# fDrive_RP2040.net
KiCad netlist of a schematic drawn in EAGLE
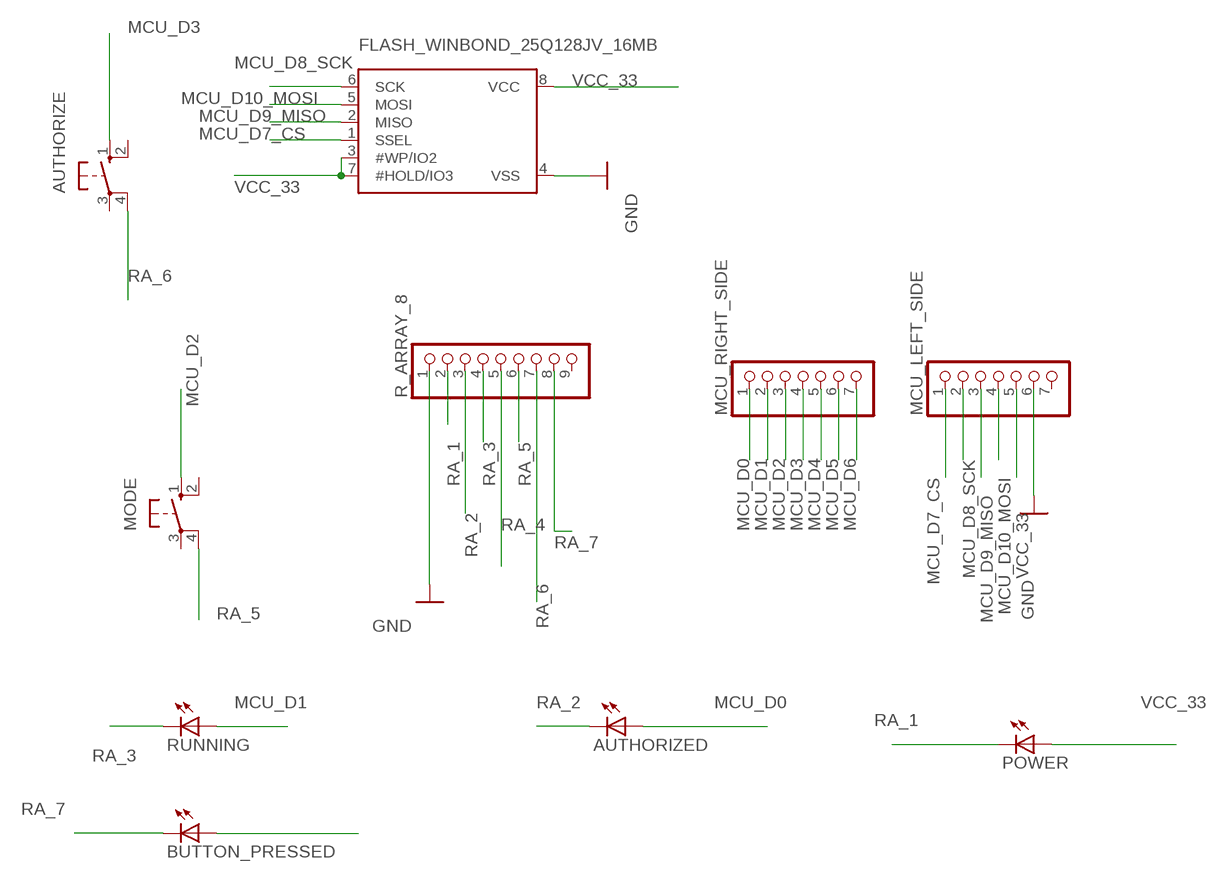
[diagram p0: schematic, sheet 1]

(export (version "E")
  (design (tool "Eeschema 10.0.6"))
  (components
    (comp (ref "AUTHORIZE")
      (value "10-XX")
      (footprint "eagle-import:B3F-10XX")
      (fields (field (name "MPN") "B3F-1000"))
      (libsource (lib "eagle-import") (part "10-XX"))
    )
    (comp (ref "AUTHORIZED")
      (value "LEDSMT1206")
      (footprint "eagle-import:1206")
      (libsource (lib "eagle-import") (part "LEDSMT1206"))
    )
    (comp (ref "BUTTON_PRESSED")
      (value "LEDSMT1206")
      (footprint "eagle-import:1206")
      (libsource (lib "eagle-import") (part "LEDSMT1206"))
    )
    (comp (ref "FLASH_WINBOND_25Q128JV_16MB")
      (value "SPIFLASH_SOIC8208MIL")
      (footprint "eagle-import:SOIC8_208MIL")
      (libsource (lib "eagle-import") (part "SPIFLASH_SOIC8208MIL"))
    )
    (comp (ref "MCU_LEFT_SIDE")
      (value "PINHD-1X7")
      (footprint "eagle-import:1X07")
      (libsource (lib "eagle-import") (part "PINHD-1X7"))
    )
    (comp (ref "MCU_RIGHT_SIDE")
      (value "PINHD-1X7")
      (footprint "eagle-import:1X07")
      (libsource (lib "eagle-import") (part "PINHD-1X7"))
    )
    (comp (ref "MODE")
      (value "10-XX")
      (footprint "eagle-import:B3F-10XX")
      (fields (field (name "MPN") "B3F-1000"))
      (libsource (lib "eagle-import") (part "10-XX"))
    )
    (comp (ref "POWER")
      (value "LEDSMT1206")
      (footprint "eagle-import:1206")
      (libsource (lib "eagle-import") (part "LEDSMT1206"))
    )
    (comp (ref "RUNNING")
      (value "LEDSMT1206")
      (footprint "eagle-import:1206")
      (libsource (lib "eagle-import") (part "LEDSMT1206"))
    )
    (comp (ref "R_ARRAY_8")
      (value "PINHD-1X9")
      (footprint "eagle-import:1X09-BIG")
      (libsource (lib "eagle-import") (part "PINHD-1X9"))
    )
  )
  (nets
    (net (code "1") (name "/MCU_D0") (class "Default")
      (node (ref "AUTHORIZED") (pin "A") (pinfunction "A_A") (pintype "passive"))
      (node (ref "MCU_RIGHT_SIDE") (pin "1") (pinfunction "1_1") (pintype "passive"))
    )
    (net (code "2") (name "/MCU_D1") (class "Default")
      (node (ref "MCU_RIGHT_SIDE") (pin "2") (pinfunction "2_2") (pintype "passive"))
      (node (ref "RUNNING") (pin "A") (pinfunction "A_A") (pintype "passive"))
    )
    (net (code "3") (name "/MCU_D2") (class "Default")
      (node (ref "MCU_RIGHT_SIDE") (pin "3") (pinfunction "3_3") (pintype "passive"))
      (node (ref "MODE") (pin "1") (pinfunction "S_1") (pintype "passive"))
    )
    (net (code "4") (name "/MCU_D3") (class "Default")
      (node (ref "AUTHORIZE") (pin "1") (pinfunction "S_1") (pintype "passive"))
      (node (ref "MCU_RIGHT_SIDE") (pin "4") (pinfunction "4_4") (pintype "passive"))
    )
    (net (code "5") (name "/MCU_D4") (class "Default")
      (node (ref "BUTTON_PRESSED") (pin "A") (pinfunction "A_A") (pintype "passive"))
      (node (ref "MCU_RIGHT_SIDE") (pin "5") (pinfunction "5_5") (pintype "passive"))
    )
    (net (code "6") (name "/MCU_D5") (class "Default")
      (node (ref "MCU_RIGHT_SIDE") (pin "6") (pinfunction "6_6") (pintype "passive"))
    )
    (net (code "7") (name "/MCU_D6") (class "Default")
      (node (ref "MCU_RIGHT_SIDE") (pin "7") (pinfunction "7_7") (pintype "passive"))
    )
    (net (code "8") (name "/MCU_D7_CS") (class "Default")
      (node (ref "FLASH_WINBOND_25Q128JV_16MB") (pin "1") (pinfunction "SSEL_1") (pintype "bidirectional"))
      (node (ref "MCU_LEFT_SIDE") (pin "1") (pinfunction "1_1") (pintype "passive"))
    )
    (net (code "9") (name "/MCU_D8_SCK") (class "Default")
      (node (ref "FLASH_WINBOND_25Q128JV_16MB") (pin "6") (pinfunction "SCK_6") (pintype "bidirectional"))
      (node (ref "MCU_LEFT_SIDE") (pin "2") (pinfunction "2_2") (pintype "passive"))
    )
    (net (code "10") (name "/MCU_D9_MISO") (class "Default")
      (node (ref "FLASH_WINBOND_25Q128JV_16MB") (pin "2") (pinfunction "MISO_2") (pintype "bidirectional"))
      (node (ref "MCU_LEFT_SIDE") (pin "3") (pinfunction "3_3") (pintype "passive"))
    )
    (net (code "11") (name "/MCU_D10_MOSI") (class "Default")
      (node (ref "FLASH_WINBOND_25Q128JV_16MB") (pin "5") (pinfunction "MOSI_5") (pintype "bidirectional"))
      (node (ref "MCU_LEFT_SIDE") (pin "4") (pinfunction "4_4") (pintype "passive"))
    )
    (net (code "12") (name "/RA_1") (class "Default")
      (node (ref "POWER") (pin "C") (pinfunction "C_C") (pintype "passive"))
      (node (ref "R_ARRAY_8") (pin "2") (pinfunction "2_2") (pintype "passive"))
    )
    (net (code "13") (name "/RA_2") (class "Default")
      (node (ref "AUTHORIZED") (pin "C") (pinfunction "C_C") (pintype "passive"))
      (node (ref "R_ARRAY_8") (pin "3") (pinfunction "3_3") (pintype "passive"))
    )
    (net (code "14") (name "/RA_3") (class "Default")
      (node (ref "RUNNING") (pin "C") (pinfunction "C_C") (pintype "passive"))
      (node (ref "R_ARRAY_8") (pin "4") (pinfunction "4_4") (pintype "passive"))
    )
    (net (code "15") (name "/RA_4") (class "Default")
      (node (ref "R_ARRAY_8") (pin "5") (pinfunction "5_5") (pintype "passive"))
    )
    (net (code "16") (name "/RA_5") (class "Default")
      (node (ref "MODE") (pin "4") (pinfunction "P1_4") (pintype "passive"))
      (node (ref "R_ARRAY_8") (pin "6") (pinfunction "6_6") (pintype "passive"))
    )
    (net (code "17") (name "/RA_6") (class "Default")
      (node (ref "AUTHORIZE") (pin "4") (pinfunction "P1_4") (pintype "passive"))
      (node (ref "R_ARRAY_8") (pin "7") (pinfunction "7_7") (pintype "passive"))
    )
    (net (code "18") (name "/RA_7") (class "Default")
      (node (ref "BUTTON_PRESSED") (pin "C") (pinfunction "C_C") (pintype "passive"))
      (node (ref "R_ARRAY_8") (pin "8") (pinfunction "8_8") (pintype "passive"))
    )
    (net (code "19") (name "/VCC_33") (class "Default")
      (node (ref "FLASH_WINBOND_25Q128JV_16MB") (pin "3") (pinfunction "#WP/IO2_3") (pintype "bidirectional"))
      (node (ref "FLASH_WINBOND_25Q128JV_16MB") (pin "7") (pinfunction "#HOLD/IO3_7") (pintype "bidirectional"))
      (node (ref "FLASH_WINBOND_25Q128JV_16MB") (pin "8") (pinfunction "VCC_8") (pintype "bidirectional"))
      (node (ref "MCU_LEFT_SIDE") (pin "5") (pinfunction "5_5") (pintype "passive"))
      (node (ref "POWER") (pin "A") (pinfunction "A_A") (pintype "passive"))
    )
    (net (code "20") (name "GND") (class "Default")
      (node (ref "FLASH_WINBOND_25Q128JV_16MB") (pin "4") (pinfunction "VSS_4") (pintype "bidirectional"))
      (node (ref "MCU_LEFT_SIDE") (pin "6") (pinfunction "6_6") (pintype "passive"))
      (node (ref "R_ARRAY_8") (pin "1") (pinfunction "1_1") (pintype "passive"))
    )
    (net (code "21") (name "unconnected-(AUTHORIZE-P-Pad3)") (class "Default")
      (node (ref "AUTHORIZE") (pin "3") (pinfunction "P_3") (pintype "passive"))
    )
    (net (code "22") (name "unconnected-(AUTHORIZE-S1-Pad2)") (class "Default")
      (node (ref "AUTHORIZE") (pin "2") (pinfunction "S1_2") (pintype "passive"))
    )
    (net (code "23") (name "unconnected-(MCU_LEFT_SIDE-Pad7)") (class "Default")
      (node (ref "MCU_LEFT_SIDE") (pin "7") (pinfunction "7_7") (pintype "passive"))
    )
    (net (code "24") (name "unconnected-(MODE-P-Pad3)") (class "Default")
      (node (ref "MODE") (pin "3") (pinfunction "P_3") (pintype "passive"))
    )
    (net (code "25") (name "unconnected-(MODE-S1-Pad2)") (class "Default")
      (node (ref "MODE") (pin "2") (pinfunction "S1_2") (pintype "passive"))
    )
    (net (code "26") (name "unconnected-(R_ARRAY_8-Pad9)") (class "Default")
      (node (ref "R_ARRAY_8") (pin "9") (pinfunction "9_9") (pintype "passive"))
    )
  )
)
